# Tiny817_Xplained_Pro_dual_input_power_su.net
KiCad netlist of a schematic drawn in Altium Designer
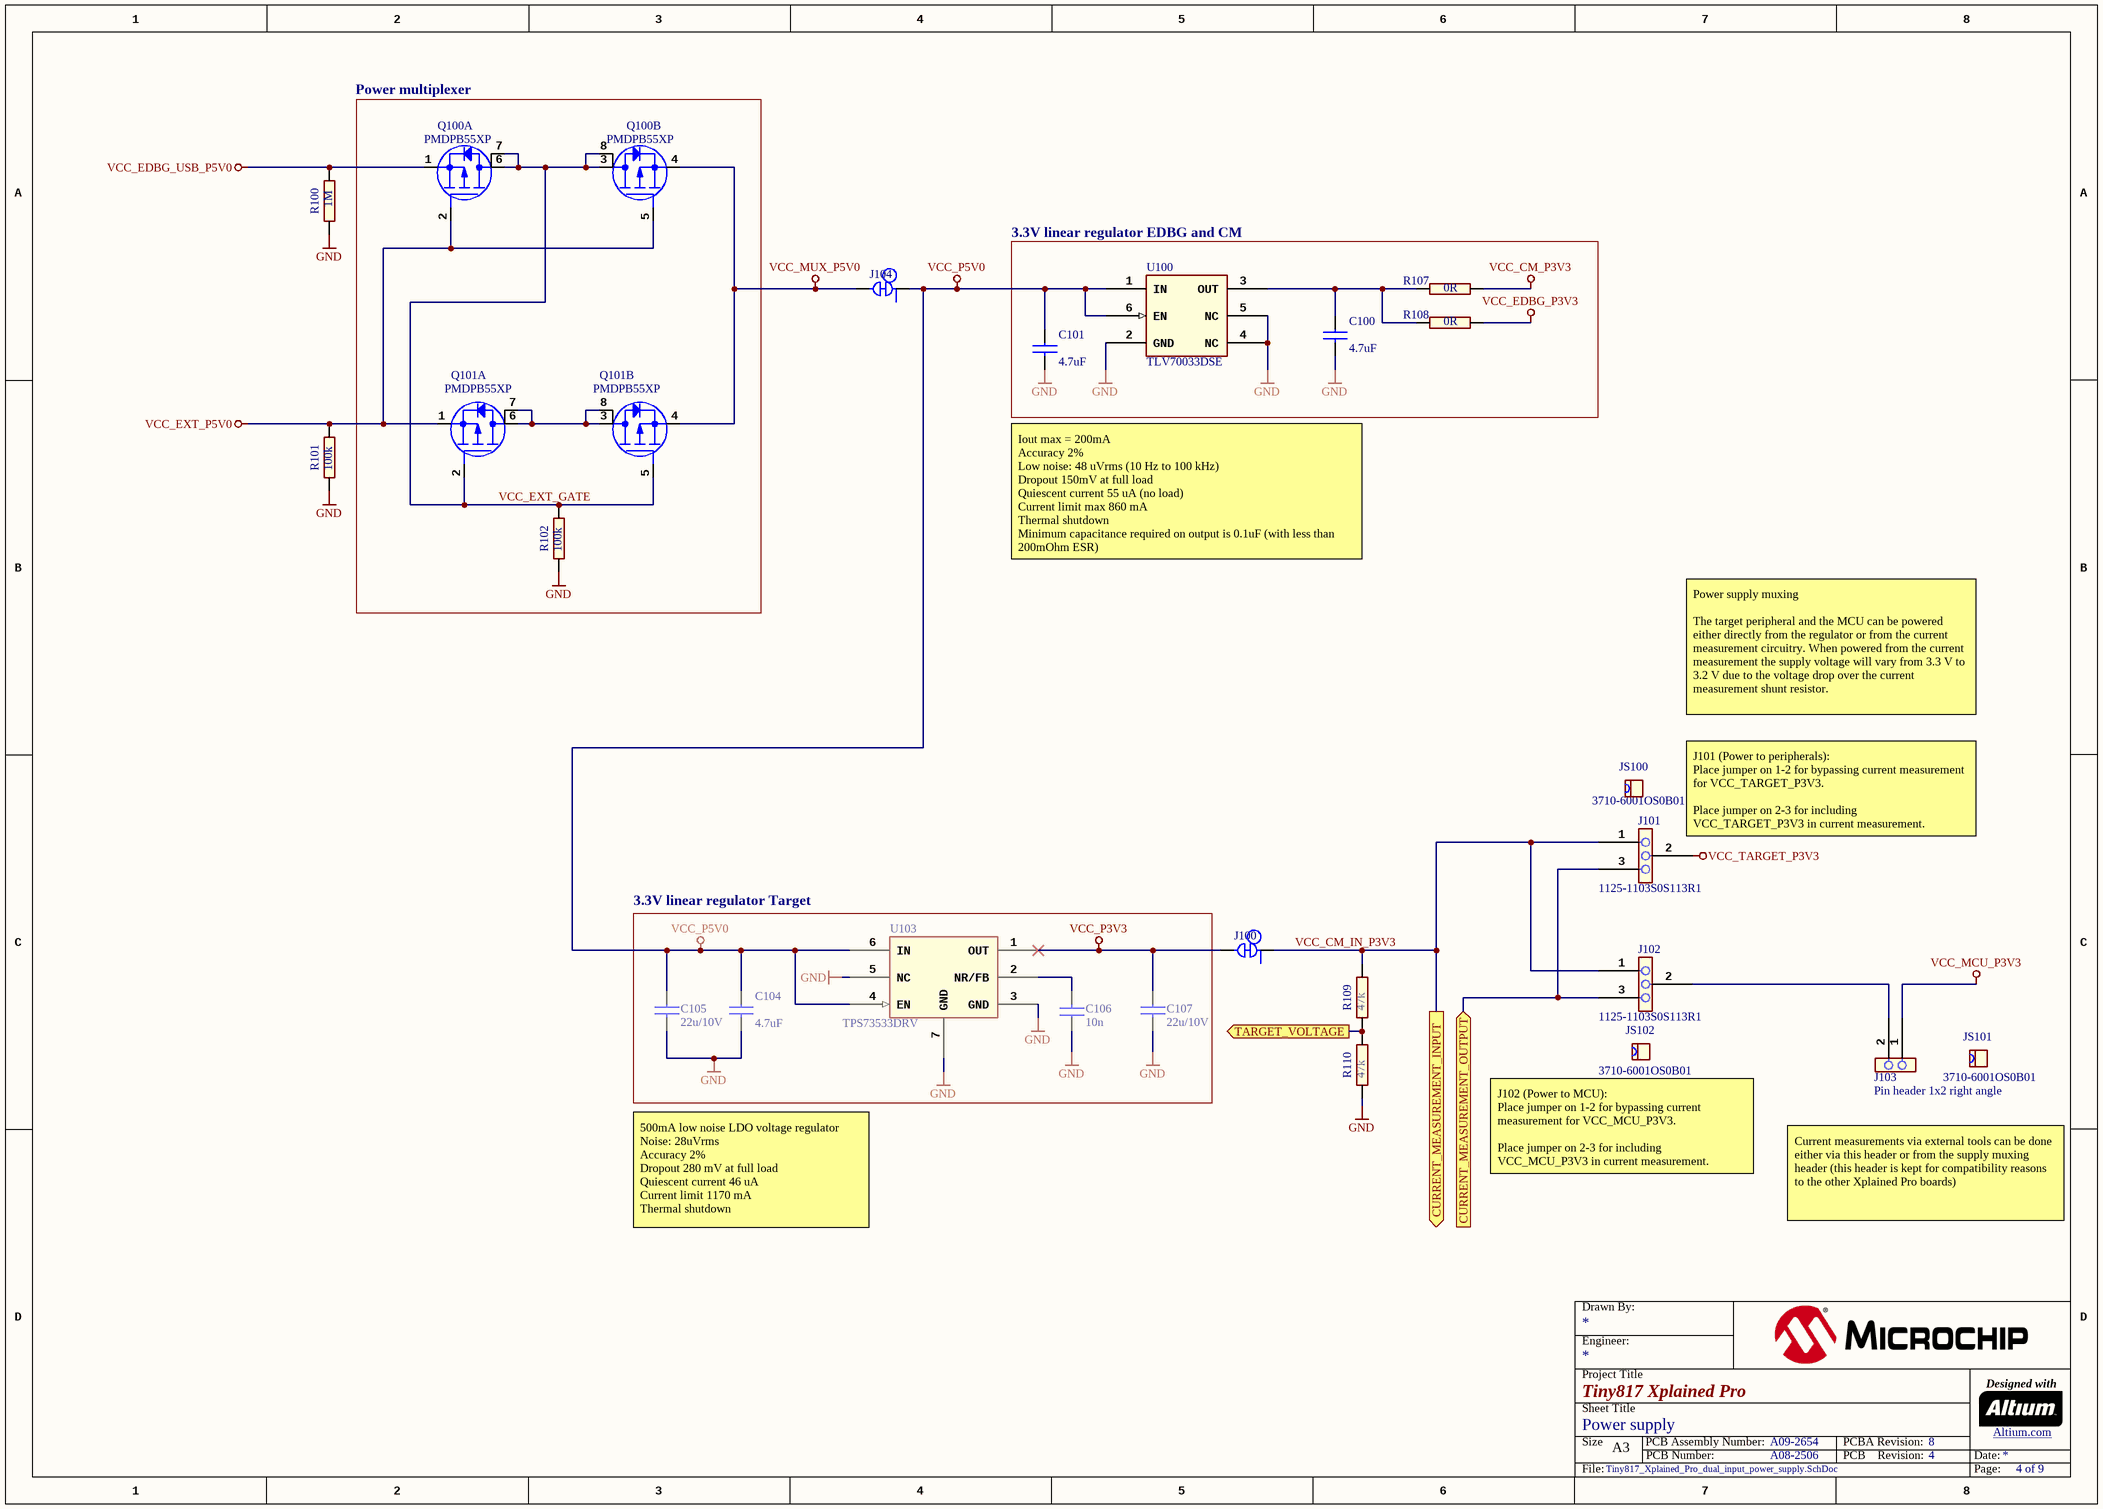
[diagram p0: Tiny817_Xplained_Pro_dual_input_power_supply.SchDoc]

(export (version "E")
  (design (tool "Eeschema 10.0.6"))
  (components
    (comp (ref "C100")
      (value "4.7uF")
      (footprint "AP1-00117")
      (description "Ceramic capacitor, SMD 0603, X5R, 10V, 10% (de31036)")
      (fields (field (name "TOLERANCE") "10%") (field (name "MANUFACTURER") "WALSIN Technology Corporation"))
      (libsource (lib "AltiumDbLib") (part "CAP-NONPOL"))
    )
    (comp (ref "C101")
      (value "4.7uF")
      (footprint "AP1-00117")
      (description "Ceramic capacitor, SMD 0603, X5R, 10V, 10% (de31036)")
      (fields (field (name "TOLERANCE") "10%") (field (name "MANUFACTURER") "WALSIN Technology Corporation"))
      (libsource (lib "AltiumDbLib") (part "CAP-NONPOL"))
    )
    (comp (ref "C104")
      (value "4.7uF")
      (footprint "AP1-00117")
      (description "Ceramic capacitor, SMD 0603, X5R, 10V, 10% (de31036)")
      (fields (field (name "TOLERANCE") "10%") (field (name "MANUFACTURER") "WALSIN Technology Corporation"))
      (libsource (lib "AltiumDbLib") (part "CAP-NONPOL"))
    )
    (comp (ref "C105")
      (value "22u/10V")
      (footprint "AP1-00003")
      (description "Ceramic capacitor, SMD 0805, X5R, 10V, Â±20%")
      (fields (field (name "MANUFACTURER") "TDK") (field (name "MPN") "C2012X5R1A226M/0.85"))
      (libsource (lib "AltiumDbLib") (part "CAP-NONPOL"))
    )
    (comp (ref "C106")
      (value "10n")
      (footprint "AP1-00053")
      (description "Ceramic capacitor, SMD 0402, X7R, 25V, +/-10%")
      (fields (field (name "TOLERANCE") "25V, +/-10%") (field (name "MANUFACTURER") "Yageo"))
      (libsource (lib "AltiumDbLib") (part "CAP-NONPOL"))
    )
    (comp (ref "C107")
      (value "22u/10V")
      (footprint "AP1-00003")
      (description "Ceramic capacitor, SMD 0805, X5R, 10V, Â±20%")
      (fields (field (name "MANUFACTURER") "TDK") (field (name "MPN") "C2012X5R1A226M/0.85"))
      (libsource (lib "AltiumDbLib") (part "CAP-NONPOL"))
    )
    (comp (ref "J100")
      (value "~")
      (footprint "AP9-00044")
      (description "Default closed SMD strap, 0603 size")
      (libsource (lib "AltiumDbLib") (part "SMD-STRAP_CLOSED"))
    )
    (comp (ref "J101")
      (value "1125-1103S0S113R1")
      (footprint "AP8-00745")
      (description "1x3 pin header, 2.54mm pitch, Pin-in-Paste THM")
      (fields (field (name "MANUFACTURER") "WCON"))
      (libsource (lib "AltiumDbLib") (part "HEADER 1x3"))
    )
    (comp (ref "J102")
      (value "1125-1103S0S113R1")
      (footprint "AP8-00745")
      (description "1x3 pin header, 2.54mm pitch, Pin-in-Paste THM")
      (fields (field (name "MANUFACTURER") "WCON"))
      (libsource (lib "AltiumDbLib") (part "HEADER 1x3"))
    )
    (comp (ref "J103")
      (value "Pin header 1x2 right angle")
      (footprint "AP8-00367")
      (description "1x2 pin header, right angle, 2.54 mm pitch, through-hole")
      (fields (field (name "MANUFACTURER") "WCON") (field (name "MPN") "1125-1102S0R138R1"))
      (libsource (lib "AltiumDbLib") (part "HEADER 1x2"))
    )
    (comp (ref "J104")
      (value "~")
      (footprint "AP9-00044")
      (description "Default closed SMD strap, 0603 size")
      (libsource (lib "AltiumDbLib") (part "SMD-STRAP_CLOSED"))
    )
    (comp (ref "JS100")
      (value "3710-6001OS0B01")
      (footprint "AP8-00525")
      (description "Jumper cap for 2.54mm pinheader")
      (fields (field (name "MANUFACTURER") "WCON"))
      (libsource (lib "AltiumDbLib") (part "JUMPER_CAP"))
    )
    (comp (ref "JS101")
      (value "3710-6001OS0B01")
      (footprint "AP8-00525")
      (description "Jumper cap for 2.54mm pinheader")
      (fields (field (name "MANUFACTURER") "WCON"))
      (libsource (lib "AltiumDbLib") (part "JUMPER_CAP"))
    )
    (comp (ref "JS102")
      (value "3710-6001OS0B01")
      (footprint "AP8-00525")
      (description "Jumper cap for 2.54mm pinheader")
      (fields (field (name "MANUFACTURER") "WCON"))
      (libsource (lib "AltiumDbLib") (part "JUMPER_CAP"))
    )
    (comp (ref "Q100")
      (value "PMDPB55XP")
      (footprint "AP5-00047")
      (description "Dual P-Channel MOSFET, -20V, RDS(ON) < 55 mOhm @-3.4A@-4.5V")
      (fields (field (name "MANUFACTURER") "NXP") (field (name "Comment") "Farnell order code: 2191806"))
      (libsource (lib "AltiumDbLib") (part "MOSFET_DUAL_P_S1G1D2S2G2D1D1D2"))
    )
    (comp (ref "Q101")
      (value "PMDPB55XP")
      (footprint "AP5-00047")
      (description "Dual P-Channel MOSFET, -20V, RDS(ON) < 55 mOhm @-3.4A@-4.5V")
      (fields (field (name "MANUFACTURER") "NXP") (field (name "Comment") "Farnell order code: 2191806"))
      (libsource (lib "AltiumDbLib") (part "MOSFET_DUAL_P_S1G1D2S2G2D1D1D2"))
    )
    (comp (ref "R100")
      (value "1M")
      (footprint "AP2-00011")
      (description "Thick film resistor, SMD 0402, 1/16W, 1%")
      (fields (field (name "TOLERANCE") "1 %") (field (name "MANUFACTURER") "ASJ Holdings"))
      (libsource (lib "AltiumDbLib") (part "R2"))
    )
    (comp (ref "R101")
      (value "100k")
      (footprint "AP2-00011")
      (description "Thick film resistor, SMD 0402, 1/16W, 1%")
      (fields (field (name "TOLERANCE") "1 %") (field (name "MANUFACTURER") "ASJ Holdings"))
      (libsource (lib "AltiumDbLib") (part "R2"))
    )
    (comp (ref "R102")
      (value "100k")
      (footprint "AP2-00011")
      (description "Thick film resistor, SMD 0402, 1/16W, 1%")
      (fields (field (name "TOLERANCE") "1 %") (field (name "MANUFACTURER") "ASJ Holdings"))
      (libsource (lib "AltiumDbLib") (part "R2"))
    )
    (comp (ref "R107")
      (value "0R")
      (footprint "AP2-00011")
      (description "RES 0.0 OHM 1/16W 0402 SMD")
      (fields (field (name "TOLERANCE") "1 %") (field (name "MANUFACTURER") "(n/a)"))
      (libsource (lib "") (part "R2_1"))
    )
    (comp (ref "R108")
      (value "0R")
      (footprint "AP2-00011")
      (description "RES 0.0 OHM 1/16W 0402 SMD")
      (fields (field (name "TOLERANCE") "1 %") (field (name "MANUFACTURER") "(n/a)"))
      (libsource (lib "") (part "R2_1"))
    )
    (comp (ref "R109")
      (value "47k")
      (footprint "AP2-00011")
      (description "Thick film resistor, SMD 0402, 1/16W, 1%")
      (fields (field (name "TOLERANCE") "1 %") (field (name "MANUFACTURER") "KOA"))
      (libsource (lib "") (part "R2_2"))
    )
    (comp (ref "R110")
      (value "47k")
      (footprint "AP2-00011")
      (description "Thick film resistor, SMD 0402, 1/16W, 1%")
      (fields (field (name "TOLERANCE") "1 %") (field (name "MANUFACTURER") "KOA"))
      (libsource (lib "") (part "R2_2"))
    )
    (comp (ref "U100")
      (value "TLV70033DSE")
      (footprint "AP6-00262")
      (description "LDO, 200 mA, Iq=31 uA, Vdo=250mV, Vout=3.3V, VIN= 2 V to 5.5V, SON-6 package")
      (fields (field (name "MANUFACTURER") "Texas Instruments"))
      (libsource (lib "AltiumDbLib") (part "TLV70033"))
    )
    (comp (ref "U103")
      (value "TPS73533DRV")
      (footprint "AP6-00162")
      (fields (field (name "MANUFACTURER") "Texas Instruments"))
      (libsource (lib "AltiumDbLib") (part "TPS735xxDRV"))
    )
  )
  (nets
    (net (code "1") (name "/CURRENT_MEASUREMENT_OUTPUT") (class "Default")
      (node (ref "J101") (pin "3") (pinfunction "3_3") (pintype "passive"))
      (node (ref "J102") (pin "3") (pinfunction "3_3") (pintype "passive"))
    )
    (net (code "2") (name "/TARGET_VOLTAGE") (class "Default")
      (node (ref "R109") (pin "1") (pinfunction "1_1") (pintype "passive"))
      (node (ref "R110") (pin "2") (pinfunction "2_2") (pintype "passive"))
    )
    (net (code "3") (name "/VCC_CM_IN_P3V3") (class "Default")
      (node (ref "J100") (pin "1") (pinfunction "1_1") (pintype "passive"))
      (node (ref "J101") (pin "1") (pinfunction "1_1") (pintype "passive"))
      (node (ref "J102") (pin "1") (pinfunction "1_1") (pintype "passive"))
      (node (ref "R109") (pin "2") (pinfunction "2_2") (pintype "passive"))
    )
    (net (code "4") (name "/VCC_EXT_GATE") (class "Default")
      (node (ref "Q100") (pin "3") (pinfunction "D2_3") (pintype "passive"))
      (node (ref "Q100") (pin "6") (pinfunction "D1_6") (pintype "passive"))
      (node (ref "Q100") (pin "7") (pinfunction "D1_PAD_7") (pintype "passive"))
      (node (ref "Q100") (pin "8") (pinfunction "D2_PAD_8") (pintype "passive"))
      (node (ref "Q101") (pin "2") (pinfunction "G1_2") (pintype "passive"))
      (node (ref "Q101") (pin "5") (pinfunction "G2_5") (pintype "passive"))
      (node (ref "R102") (pin "2") (pinfunction "2_2") (pintype "passive"))
    )
    (net (code "5") (name "GND") (class "Default")
      (node (ref "C100") (pin "2") (pinfunction "2_2") (pintype "passive"))
      (node (ref "C101") (pin "2") (pinfunction "2_2") (pintype "passive"))
      (node (ref "C104") (pin "2") (pinfunction "2_2") (pintype "passive"))
      (node (ref "C105") (pin "2") (pinfunction "2_2") (pintype "passive"))
      (node (ref "C106") (pin "1") (pinfunction "1_1") (pintype "passive"))
      (node (ref "C107") (pin "2") (pinfunction "2_2") (pintype "passive"))
      (node (ref "R100") (pin "1") (pinfunction "1_1") (pintype "passive"))
      (node (ref "R101") (pin "1") (pinfunction "1_1") (pintype "passive"))
      (node (ref "R102") (pin "1") (pinfunction "1_1") (pintype "passive"))
      (node (ref "R110") (pin "1") (pinfunction "1_1") (pintype "passive"))
      (node (ref "U100") (pin "2") (pinfunction "GND_2") (pintype "power_in"))
      (node (ref "U100") (pin "4") (pinfunction "NC_4") (pintype "passive"))
      (node (ref "U100") (pin "5") (pinfunction "NC_5") (pintype "passive"))
      (node (ref "U103") (pin "3") (pinfunction "GND_3") (pintype "power_in"))
      (node (ref "U103") (pin "5") (pinfunction "NC_5") (pintype "passive"))
      (node (ref "U103") (pin "7") (pinfunction "GND_7") (pintype "power_in"))
    )
    (net (code "6") (name "Net-(J102-Pad2)") (class "Default")
      (node (ref "J102") (pin "2") (pinfunction "2_2") (pintype "passive"))
      (node (ref "J103") (pin "2") (pinfunction "2_2") (pintype "passive"))
    )
    (net (code "7") (name "Net-(Q101A-D1)") (class "Default")
      (node (ref "Q101") (pin "3") (pinfunction "D2_3") (pintype "passive"))
      (node (ref "Q101") (pin "6") (pinfunction "D1_6") (pintype "passive"))
      (node (ref "Q101") (pin "7") (pinfunction "D1_PAD_7") (pintype "passive"))
      (node (ref "Q101") (pin "8") (pinfunction "D2_PAD_8") (pintype "passive"))
    )
    (net (code "8") (name "Net-(U100-OUT)") (class "Default")
      (node (ref "C100") (pin "1") (pinfunction "1_1") (pintype "passive"))
      (node (ref "R107") (pin "2") (pinfunction "2_2") (pintype "passive"))
      (node (ref "R108") (pin "2") (pinfunction "2_2") (pintype "passive"))
      (node (ref "U100") (pin "3") (pinfunction "OUT_3") (pintype "power_in"))
    )
    (net (code "9") (name "Net-(U103-NR{slash}FB)") (class "Default")
      (node (ref "C106") (pin "2") (pinfunction "2_2") (pintype "passive"))
      (node (ref "U103") (pin "2") (pinfunction "NR/FB_2") (pintype "passive"))
    )
    (net (code "10") (name "VCC_CM_P3V3") (class "Default")
      (node (ref "R107") (pin "1") (pinfunction "1_1") (pintype "passive"))
    )
    (net (code "11") (name "VCC_EDBG_P3V3") (class "Default")
      (node (ref "R108") (pin "1") (pinfunction "1_1") (pintype "passive"))
    )
    (net (code "12") (name "VCC_EDBG_USB_P5V0") (class "Default")
      (node (ref "Q100") (pin "1") (pinfunction "S1_1") (pintype "passive"))
      (node (ref "R100") (pin "2") (pinfunction "2_2") (pintype "passive"))
    )
    (net (code "13") (name "VCC_EXT_P5V0") (class "Default")
      (node (ref "Q100") (pin "2") (pinfunction "G1_2") (pintype "passive"))
      (node (ref "Q100") (pin "5") (pinfunction "G2_5") (pintype "passive"))
      (node (ref "Q101") (pin "1") (pinfunction "S1_1") (pintype "passive"))
      (node (ref "R101") (pin "2") (pinfunction "2_2") (pintype "passive"))
    )
    (net (code "14") (name "VCC_MCU_P3V3") (class "Default")
      (node (ref "J103") (pin "1") (pinfunction "1_1") (pintype "passive"))
    )
    (net (code "15") (name "VCC_MUX_P5V0") (class "Default")
      (node (ref "J104") (pin "2") (pinfunction "2_2") (pintype "passive"))
      (node (ref "Q100") (pin "4") (pinfunction "S2_4") (pintype "passive"))
      (node (ref "Q101") (pin "4") (pinfunction "S2_4") (pintype "passive"))
    )
    (net (code "16") (name "VCC_P3V3") (class "Default")
      (node (ref "C107") (pin "1") (pinfunction "1_1") (pintype "passive"))
      (node (ref "J100") (pin "2") (pinfunction "2_2") (pintype "passive"))
      (node (ref "U103") (pin "1") (pinfunction "OUT_1") (pintype "power_in"))
    )
    (net (code "17") (name "VCC_P5V0") (class "Default")
      (node (ref "C101") (pin "1") (pinfunction "1_1") (pintype "passive"))
      (node (ref "C104") (pin "1") (pinfunction "1_1") (pintype "passive"))
      (node (ref "C105") (pin "1") (pinfunction "1_1") (pintype "passive"))
      (node (ref "J104") (pin "1") (pinfunction "1_1") (pintype "passive"))
      (node (ref "U100") (pin "1") (pinfunction "IN_1") (pintype "power_in"))
      (node (ref "U100") (pin "6") (pinfunction "EN_6") (pintype "input"))
      (node (ref "U103") (pin "4") (pinfunction "EN_4") (pintype "input"))
      (node (ref "U103") (pin "6") (pinfunction "IN_6") (pintype "power_in"))
    )
    (net (code "18") (name "VCC_TARGET_P3V3") (class "Default")
      (node (ref "J101") (pin "2") (pinfunction "2_2") (pintype "passive"))
    )
  )
)
